# CAT24C32_Breakout.net
KiCad netlist of a schematic drawn in Altium Designer
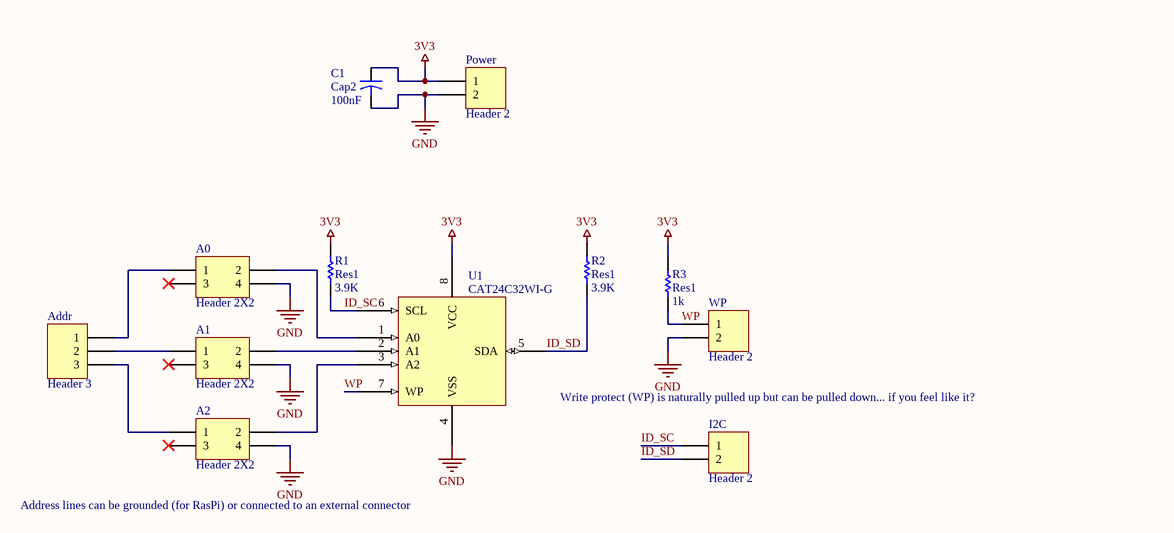
[diagram p0: CAT24C32 Breakout.SchDoc]

(export (version "E")
  (design (tool "Eeschema 10.0.6"))
  (components
    (comp (ref "A0")
      (value "Header 2X2")
      (footprint "HDR2X2")
      (description "Header, 2-Pin, Dual row")
      (fields (field (name "PUBLISHER") "Altium Limited"))
      (libsource (lib "Miscellaneous Connectors") (part "Header 2X2"))
    )
    (comp (ref "A1")
      (value "Header 2X2")
      (footprint "HDR2X2")
      (description "Header, 2-Pin, Dual row")
      (fields (field (name "PUBLISHER") "Altium Limited"))
      (libsource (lib "Miscellaneous Connectors") (part "Header 2X2"))
    )
    (comp (ref "A2")
      (value "Header 2X2")
      (footprint "HDR2X2")
      (description "Header, 2-Pin, Dual row")
      (fields (field (name "PUBLISHER") "Altium Limited"))
      (libsource (lib "Miscellaneous Connectors") (part "Header 2X2"))
    )
    (comp (ref "Addr")
      (value "Header 3")
      (footprint "HDR1X3")
      (description "Header, 3-Pin")
      (fields (field (name "PUBLISHER") "Altium Limited"))
      (libsource (lib "Miscellaneous Connectors") (part "Header 3"))
    )
    (comp (ref "C1")
      (value "Cap2")
      (footprint "CAPR5-4X5")
      (description "Capacitor")
      (fields (field (name "ALTIUM_VALUE") "100nF") (field (name "PUBLISHER") "Altium Limited"))
      (libsource (lib "Miscellaneous Devices") (part "Cap2"))
    )
    (comp (ref "I2C")
      (value "Header 2")
      (footprint "HDR1X2")
      (description "Header, 2-Pin")
      (fields (field (name "PUBLISHER") "Altium Limited"))
      (libsource (lib "Miscellaneous Connectors") (part "Header 2"))
    )
    (comp (ref "Power")
      (value "Header 2")
      (footprint "HDR1X2")
      (description "Header, 2-Pin")
      (fields (field (name "PUBLISHER") "Altium Limited"))
      (libsource (lib "Miscellaneous Connectors") (part "Header 2"))
    )
    (comp (ref "R1")
      (value "Res1")
      (footprint "AXIAL-0.3")
      (description "Resistor")
      (fields (field (name "ALTIUM_VALUE") "3.9K") (field (name "PUBLISHER") "Altium Limited"))
      (libsource (lib "Miscellaneous Devices") (part "Res1"))
    )
    (comp (ref "R2")
      (value "Res1")
      (footprint "AXIAL-0.3")
      (description "Resistor")
      (fields (field (name "ALTIUM_VALUE") "3.9K") (field (name "PUBLISHER") "Altium Limited"))
      (libsource (lib "Miscellaneous Devices") (part "Res1"))
    )
    (comp (ref "R3")
      (value "Res1")
      (footprint "AXIAL-0.3")
      (description "Resistor")
      (fields (field (name "ALTIUM_VALUE") "1k") (field (name "PUBLISHER") "Altium Limited"))
      (libsource (lib "Miscellaneous Devices") (part "Res1"))
    )
    (comp (ref "U1")
      (value "CAT24C32WI-G")
      (footprint "CAT24C32WI-G")
      (description "IC EEPROM 32KBIT 400KHZ 8SOIC")
      (libsource (lib "SwedishHat Altium Parts") (part "CAT24C32WI-G"))
    )
    (comp (ref "WP")
      (value "Header 2")
      (footprint "HDR1X2")
      (description "Header, 2-Pin")
      (fields (field (name "PUBLISHER") "Altium Limited"))
      (libsource (lib "Miscellaneous Connectors") (part "Header 2"))
    )
  )
  (nets
    (net (code "1") (name "/ID_SC") (class "Default")
      (node (ref "I2C") (pin "1") (pinfunction "1_1") (pintype "passive"))
      (node (ref "R1") (pin "1") (pinfunction "1_1") (pintype "passive"))
      (node (ref "U1") (pin "6") (pinfunction "SCL_6") (pintype "input"))
    )
    (net (code "2") (name "/ID_SD") (class "Default")
      (node (ref "I2C") (pin "2") (pinfunction "2_2") (pintype "passive"))
      (node (ref "R2") (pin "1") (pinfunction "1_1") (pintype "passive"))
      (node (ref "U1") (pin "5") (pinfunction "SDA_5") (pintype "bidirectional"))
    )
    (net (code "3") (name "/WP") (class "Default")
      (node (ref "R3") (pin "1") (pinfunction "1_1") (pintype "passive"))
      (node (ref "U1") (pin "7") (pinfunction "WP_7") (pintype "input"))
      (node (ref "WP") (pin "1") (pinfunction "1_1") (pintype "passive"))
    )
    (net (code "4") (name "3V3") (class "Default")
      (node (ref "C1") (pin "1") (pinfunction "1_1") (pintype "passive"))
      (node (ref "Power") (pin "1") (pinfunction "1_1") (pintype "passive"))
      (node (ref "R1") (pin "2") (pinfunction "2_2") (pintype "passive"))
      (node (ref "R2") (pin "2") (pinfunction "2_2") (pintype "passive"))
      (node (ref "R3") (pin "2") (pinfunction "2_2") (pintype "passive"))
      (node (ref "U1") (pin "8") (pinfunction "VCC_8") (pintype "power_in"))
    )
    (net (code "5") (name "GND") (class "Default")
      (node (ref "A0") (pin "4") (pinfunction "4_4") (pintype "passive"))
      (node (ref "A1") (pin "4") (pinfunction "4_4") (pintype "passive"))
      (node (ref "A2") (pin "4") (pinfunction "4_4") (pintype "passive"))
      (node (ref "C1") (pin "2") (pinfunction "2_2") (pintype "passive"))
      (node (ref "Power") (pin "2") (pinfunction "2_2") (pintype "passive"))
      (node (ref "U1") (pin "4") (pinfunction "VSS_4") (pintype "power_in"))
      (node (ref "WP") (pin "2") (pinfunction "2_2") (pintype "passive"))
    )
    (net (code "6") (name "Net-(A0-Pad1)") (class "Default")
      (node (ref "A0") (pin "1") (pinfunction "1_1") (pintype "passive"))
      (node (ref "Addr") (pin "1") (pinfunction "1_1") (pintype "passive"))
    )
    (net (code "7") (name "Net-(A1-Pad1)") (class "Default")
      (node (ref "A1") (pin "1") (pinfunction "1_1") (pintype "passive"))
      (node (ref "Addr") (pin "2") (pinfunction "2_2") (pintype "passive"))
    )
    (net (code "8") (name "Net-(A2-Pad1)") (class "Default")
      (node (ref "A2") (pin "1") (pinfunction "1_1") (pintype "passive"))
      (node (ref "Addr") (pin "3") (pinfunction "3_3") (pintype "passive"))
    )
    (net (code "9") (name "Net-(U1-A0)") (class "Default")
      (node (ref "A0") (pin "2") (pinfunction "2_2") (pintype "passive"))
      (node (ref "U1") (pin "1") (pinfunction "A0_1") (pintype "input"))
    )
    (net (code "10") (name "Net-(U1-A1)") (class "Default")
      (node (ref "A1") (pin "2") (pinfunction "2_2") (pintype "passive"))
      (node (ref "U1") (pin "2") (pinfunction "A1_2") (pintype "input"))
    )
    (net (code "11") (name "Net-(U1-A2)") (class "Default")
      (node (ref "A2") (pin "2") (pinfunction "2_2") (pintype "passive"))
      (node (ref "U1") (pin "3") (pinfunction "A2_3") (pintype "input"))
    )
    (net (code "12") (name "unconnected-(A0-Pad3)") (class "Default")
      (node (ref "A0") (pin "3") (pinfunction "3_3") (pintype "passive+no_connect"))
    )
    (net (code "13") (name "unconnected-(A1-Pad3)") (class "Default")
      (node (ref "A1") (pin "3") (pinfunction "3_3") (pintype "passive+no_connect"))
    )
    (net (code "14") (name "unconnected-(A2-Pad3)") (class "Default")
      (node (ref "A2") (pin "3") (pinfunction "3_3") (pintype "passive+no_connect"))
    )
  )
)
